# 1932dev.net
KiCad netlist of a schematic drawn in EAGLE
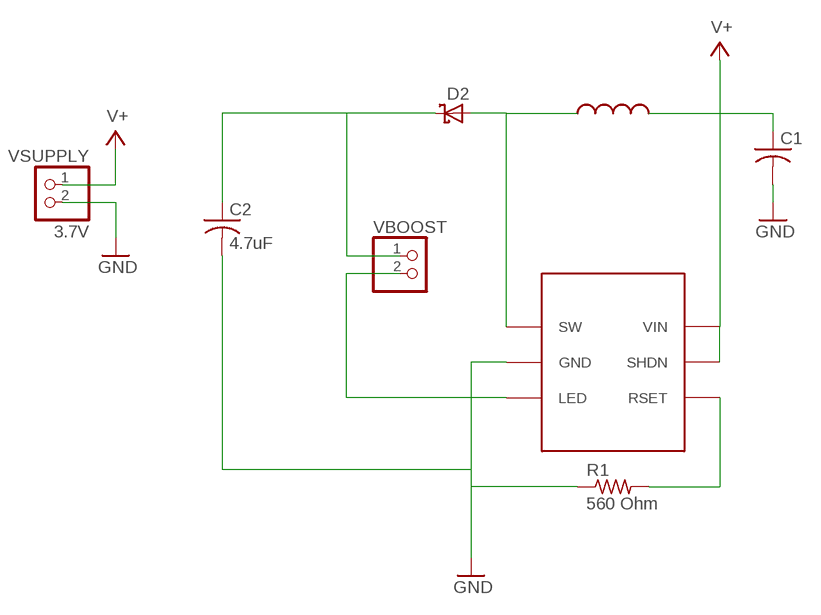
[diagram p0: schematic, sheet 1]

(export (version "E")
  (design (tool "Eeschema 10.0.6"))
  (components
    (comp (ref "C1")
      (value "C-USC0805")
      (footprint "eagle-import:C0805")
      (libsource (lib "eagle-import") (part "C-USC0805"))
    )
    (comp (ref "C2")
      (value "4.7uF")
      (footprint "eagle-import:C0805")
      (libsource (lib "eagle-import") (part "C-USC0805"))
    )
    (comp (ref "D2")
      (value "SCHOTTKY-DIODE")
      (footprint "eagle-import:SOD-323")
      (libsource (lib "eagle-import") (part "SCHOTTKY-DIODE"))
    )
    (comp (ref "L1")
      (value "10uH")
      (footprint "eagle-import:682C")
      (libsource (lib "eagle-import") (part "MURATA_11R103C"))
    )
    (comp (ref "R1")
      (value "560 Ohm")
      (footprint "eagle-import:0411V")
      (libsource (lib "eagle-import") (part "R-US_0411/3V"))
    )
    (comp (ref "U$1")
      (value "LT1932ES")
      (footprint "eagle-import:6PIN_SOT23")
      (libsource (lib "eagle-import") (part "LT1932ES"))
    )
    (comp (ref "VBOOST")
      (value "PINHD-1X2")
      (footprint "eagle-import:1X02")
      (libsource (lib "eagle-import") (part "PINHD-1X2"))
    )
    (comp (ref "VSUPPLY")
      (value "3.7V")
      (footprint "eagle-import:1X02")
      (libsource (lib "eagle-import") (part "PINHD-1X2"))
    )
  )
  (nets
    (net (code "1") (name "GND") (class "Default")
      (node (ref "C1") (pin "2") (pinfunction "2_2") (pintype "passive"))
      (node (ref "C2") (pin "2") (pinfunction "2_2") (pintype "passive"))
      (node (ref "R1") (pin "1") (pinfunction "1_1") (pintype "passive"))
      (node (ref "U$1") (pin "PIN_2") (pinfunction "GND_PIN_2") (pintype "bidirectional"))
      (node (ref "VSUPPLY") (pin "2") (pinfunction "2_2") (pintype "passive"))
    )
    (net (code "2") (name "Net-(C2-Pad1)") (class "Default")
      (node (ref "C2") (pin "1") (pinfunction "1_1") (pintype "passive"))
      (node (ref "D2") (pin "C") (pinfunction "C_C") (pintype "passive"))
      (node (ref "VBOOST") (pin "1") (pinfunction "1_1") (pintype "passive"))
    )
    (net (code "3") (name "Net-(L1-PIN_1)") (class "Default")
      (node (ref "D2") (pin "A") (pinfunction "A_A") (pintype "passive"))
      (node (ref "L1") (pin "P$3") (pinfunction "PIN_1_P$3") (pintype "bidirectional"))
      (node (ref "U$1") (pin "PIN_1") (pinfunction "SW_PIN_1") (pintype "bidirectional"))
    )
    (net (code "4") (name "Net-(U$1-LED)") (class "Default")
      (node (ref "U$1") (pin "PIN_3") (pinfunction "LED_PIN_3") (pintype "bidirectional"))
      (node (ref "VBOOST") (pin "2") (pinfunction "2_2") (pintype "passive"))
    )
    (net (code "5") (name "Net-(U$1-RSET)") (class "Default")
      (node (ref "R1") (pin "2") (pinfunction "2_2") (pintype "passive"))
      (node (ref "U$1") (pin "PIN_4") (pinfunction "RSET_PIN_4") (pintype "bidirectional"))
    )
    (net (code "6") (name "V+") (class "Default")
      (node (ref "C1") (pin "1") (pinfunction "1_1") (pintype "passive"))
      (node (ref "L1") (pin "P$4") (pinfunction "PIN_2_P$4") (pintype "bidirectional"))
      (node (ref "U$1") (pin "PIN_5") (pinfunction "SHDN_PIN_5") (pintype "bidirectional"))
      (node (ref "U$1") (pin "PIN_6") (pinfunction "VIN_PIN_6") (pintype "bidirectional"))
      (node (ref "VSUPPLY") (pin "1") (pinfunction "1_1") (pintype "passive"))
    )
  )
)
